# invamp.net
KiCad netlist of a schematic drawn in EAGLE
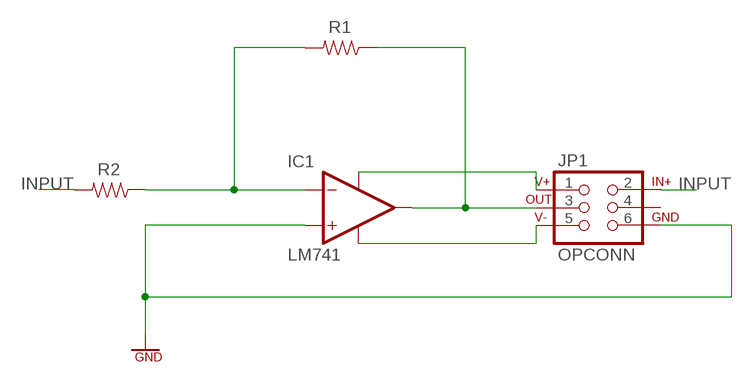
[diagram p0: schematic, sheet 1]

(export (version "E")
  (design (tool "Eeschema 10.0.6"))
  (components
    (comp (ref "IC1")
      (value "LM741")
      (footprint "eagle-import:SO08")
      (libsource (lib "eagle-import") (part "LM741"))
    )
    (comp (ref "JP1")
      (value "OPCONN")
      (footprint "eagle-import:2X3")
      (libsource (lib "eagle-import") (part "OPCONN"))
    )
    (comp (ref "R1")
      (value "RES_0603")
      (footprint "eagle-import:SMD0603")
      (libsource (lib "eagle-import") (part "RES_0603"))
    )
    (comp (ref "R2")
      (value "RES_0603")
      (footprint "eagle-import:SMD0603")
      (libsource (lib "eagle-import") (part "RES_0603"))
    )
  )
  (nets
    (net (code "1") (name "/INPUT") (class "Default")
      (node (ref "JP1") (pin "2") (pinfunction "2_2") (pintype "passive"))
      (node (ref "R2") (pin "2") (pinfunction "2_2") (pintype "passive"))
    )
    (net (code "2") (name "GND") (class "Default")
      (node (ref "IC1") (pin "3") (pinfunction "IN+_3") (pintype "input"))
      (node (ref "JP1") (pin "6") (pinfunction "6_6") (pintype "passive"))
    )
    (net (code "3") (name "Net-(IC1-IN-)") (class "Default")
      (node (ref "IC1") (pin "2") (pinfunction "IN-_2") (pintype "input"))
      (node (ref "R1") (pin "2") (pinfunction "2_2") (pintype "passive"))
      (node (ref "R2") (pin "1") (pinfunction "1_1") (pintype "passive"))
    )
    (net (code "4") (name "Net-(IC1-OUT)") (class "Default")
      (node (ref "IC1") (pin "6") (pinfunction "OUT_6") (pintype "output"))
      (node (ref "JP1") (pin "3") (pinfunction "3_3") (pintype "passive"))
      (node (ref "R1") (pin "1") (pinfunction "1_1") (pintype "passive"))
    )
    (net (code "5") (name "Net-(IC1-V+)") (class "Default")
      (node (ref "IC1") (pin "7") (pinfunction "V+_7") (pintype "power_in"))
      (node (ref "JP1") (pin "1") (pinfunction "1_1") (pintype "passive"))
    )
    (net (code "6") (name "Net-(IC1-V-)") (class "Default")
      (node (ref "IC1") (pin "4") (pinfunction "V-_4") (pintype "power_in"))
      (node (ref "JP1") (pin "5") (pinfunction "5_5") (pintype "passive"))
    )
    (net (code "7") (name "unconnected-(JP1-Pad4)") (class "Default")
      (node (ref "JP1") (pin "4") (pinfunction "4_4") (pintype "passive"))
    )
  )
)
